# Wrinkles.net
KiCad netlist of a schematic drawn in EAGLE
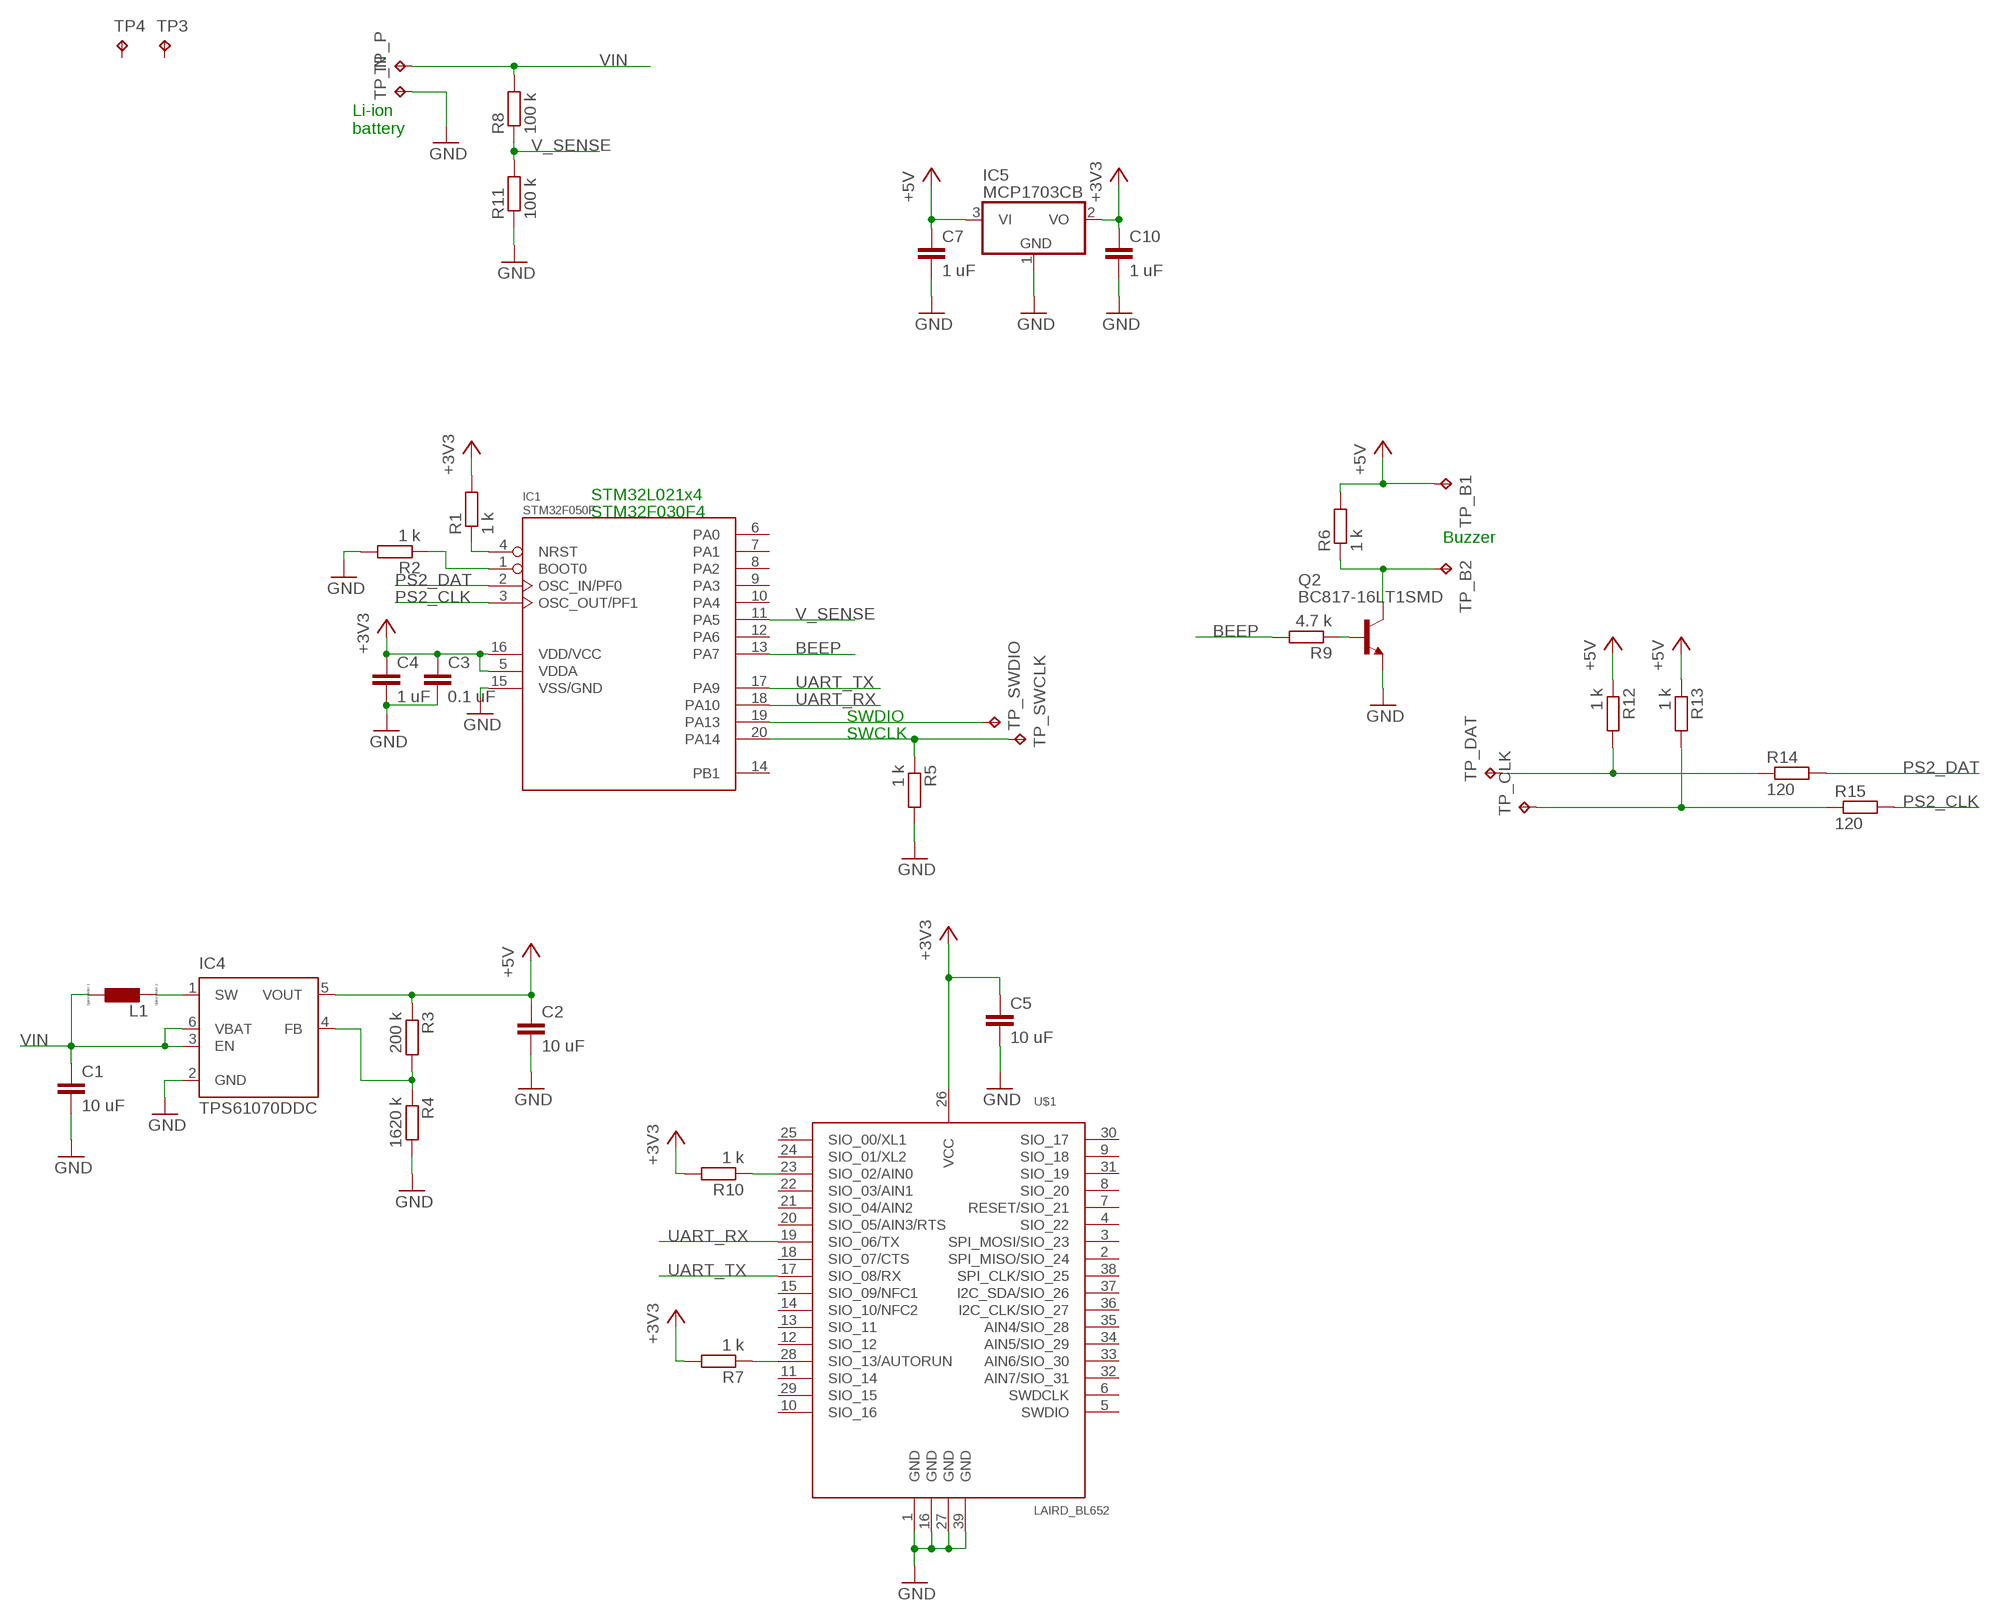
[diagram p0: schematic, sheet 1]

(export (version "E")
  (design (tool "Eeschema 10.0.6"))
  (components
    (comp (ref "C1")
      (value "10 uF")
      (footprint "eagle-import:C0603")
      (libsource (lib "eagle-import") (part "C-EUC0603"))
    )
    (comp (ref "C2")
      (value "10 uF")
      (footprint "eagle-import:C0603")
      (libsource (lib "eagle-import") (part "C-EUC0603"))
    )
    (comp (ref "C3")
      (value "0.1 uF")
      (footprint "eagle-import:C0402")
      (libsource (lib "eagle-import") (part "C-EUC0402"))
    )
    (comp (ref "C4")
      (value "1 uF")
      (footprint "eagle-import:C0402")
      (libsource (lib "eagle-import") (part "C-EUC0402"))
    )
    (comp (ref "C5")
      (value "10 uF")
      (footprint "eagle-import:C0603")
      (libsource (lib "eagle-import") (part "C-EUC0603"))
    )
    (comp (ref "C7")
      (value "1 uF")
      (footprint "eagle-import:C0402")
      (libsource (lib "eagle-import") (part "C-EUC0402"))
    )
    (comp (ref "C10")
      (value "1 uF")
      (footprint "eagle-import:C0402")
      (libsource (lib "eagle-import") (part "C-EUC0402"))
    )
    (comp (ref "IC1")
      (value "STM32F050F")
      (footprint "eagle-import:TSSOP20")
      (libsource (lib "eagle-import") (part "STM32F050F"))
    )
    (comp (ref "IC4")
      (value "TPS61070DDC")
      (footprint "eagle-import:TSOT23-6_DDC")
      (fields (field (name "MPN") "TPS61070DDCR"))
      (libsource (lib "eagle-import") (part "TPS6107DDC0"))
    )
    (comp (ref "IC5")
      (value "MCP1703CB")
      (footprint "eagle-import:SOT23")
      (libsource (lib "eagle-import") (part "MCP1703CB"))
    )
    (comp (ref "L1")
      (value "LL5038P")
      (footprint "eagle-import:L5038P")
      (libsource (lib "eagle-import") (part "LL5038P"))
    )
    (comp (ref "Q2")
      (value "BC817-16LT1SMD")
      (footprint "eagle-import:SOT23-BEC")
      (libsource (lib "eagle-import") (part "BC817SMD-16LT1"))
    )
    (comp (ref "R1")
      (value "1 k")
      (footprint "eagle-import:R0402")
      (libsource (lib "eagle-import") (part "R-EU_R0402"))
    )
    (comp (ref "R2")
      (value "1 k")
      (footprint "eagle-import:R0402")
      (libsource (lib "eagle-import") (part "R-EU_R0402"))
    )
    (comp (ref "R3")
      (value "200 k")
      (footprint "eagle-import:R0603")
      (libsource (lib "eagle-import") (part "R-EU_R0603"))
    )
    (comp (ref "R4")
      (value "1620 k")
      (footprint "eagle-import:R0603")
      (libsource (lib "eagle-import") (part "R-EU_R0603"))
    )
    (comp (ref "R5")
      (value "1 k")
      (footprint "eagle-import:R0402")
      (libsource (lib "eagle-import") (part "R-EU_R0402"))
    )
    (comp (ref "R6")
      (value "1 k")
      (footprint "eagle-import:R0402")
      (libsource (lib "eagle-import") (part "R-EU_R0402"))
    )
    (comp (ref "R7")
      (value "1 k")
      (footprint "eagle-import:R0402")
      (libsource (lib "eagle-import") (part "R-EU_R0402"))
    )
    (comp (ref "R8")
      (value "100 k")
      (footprint "eagle-import:R0402")
      (libsource (lib "eagle-import") (part "R-EU_R0402"))
    )
    (comp (ref "R9")
      (value "4.7 k")
      (footprint "eagle-import:R0402")
      (libsource (lib "eagle-import") (part "R-EU_R0402"))
    )
    (comp (ref "R10")
      (value "1 k")
      (footprint "eagle-import:R0402")
      (libsource (lib "eagle-import") (part "R-EU_R0402"))
    )
    (comp (ref "R11")
      (value "100 k")
      (footprint "eagle-import:R0402")
      (libsource (lib "eagle-import") (part "R-EU_R0402"))
    )
    (comp (ref "R12")
      (value "1 k")
      (footprint "eagle-import:R0402")
      (libsource (lib "eagle-import") (part "R-EU_R0402"))
    )
    (comp (ref "R13")
      (value "1 k")
      (footprint "eagle-import:R0402")
      (libsource (lib "eagle-import") (part "R-EU_R0402"))
    )
    (comp (ref "R14")
      (value "120")
      (footprint "eagle-import:R0402")
      (libsource (lib "eagle-import") (part "R-EU_R0402"))
    )
    (comp (ref "R15")
      (value "120")
      (footprint "eagle-import:R0402")
      (libsource (lib "eagle-import") (part "R-EU_R0402"))
    )
    (comp (ref "TP3")
      (value "TPPAD1-13")
      (footprint "eagle-import:P1-13")
      (libsource (lib "eagle-import") (part "TPPAD1-13"))
    )
    (comp (ref "TP4")
      (value "TPPAD1-13")
      (footprint "eagle-import:P1-13")
      (libsource (lib "eagle-import") (part "TPPAD1-13"))
    )
    (comp (ref "TP_B1")
      (value "TPPAD1-13")
      (footprint "eagle-import:P1-13")
      (libsource (lib "eagle-import") (part "TPPAD1-13"))
    )
    (comp (ref "TP_B2")
      (value "TPPAD1-13")
      (footprint "eagle-import:P1-13")
      (libsource (lib "eagle-import") (part "TPPAD1-13"))
    )
    (comp (ref "TP_CLK")
      (value "TPTP10SQ")
      (footprint "eagle-import:TP10SQ")
      (libsource (lib "eagle-import") (part "TPTP10SQ"))
    )
    (comp (ref "TP_DAT")
      (value "TPTP10SQ")
      (footprint "eagle-import:TP10SQ")
      (libsource (lib "eagle-import") (part "TPTP10SQ"))
    )
    (comp (ref "TP_N")
      (value "TPPAD1-13")
      (footprint "eagle-import:P1-13")
      (libsource (lib "eagle-import") (part "TPPAD1-13"))
    )
    (comp (ref "TP_P")
      (value "TPPAD1-13")
      (footprint "eagle-import:P1-13")
      (libsource (lib "eagle-import") (part "TPPAD1-13"))
    )
    (comp (ref "TP_SWCLK")
      (value "TPTP10SQ")
      (footprint "eagle-import:TP10SQ")
      (libsource (lib "eagle-import") (part "TPTP10SQ"))
    )
    (comp (ref "TP_SWDIO")
      (value "TPTP10SQ")
      (footprint "eagle-import:TP10SQ")
      (libsource (lib "eagle-import") (part "TPTP10SQ"))
    )
    (comp (ref "U$1")
      (value "LAIRD_BL652")
      (footprint "eagle-import:BL652")
      (libsource (lib "eagle-import") (part "LAIRD_BL652"))
    )
  )
  (nets
    (net (code "1") (name "+3V3") (class "Default")
      (node (ref "C10") (pin "1") (pinfunction "1_1") (pintype "passive"))
      (node (ref "C3") (pin "1") (pinfunction "1_1") (pintype "passive"))
      (node (ref "C4") (pin "1") (pinfunction "1_1") (pintype "passive"))
      (node (ref "C5") (pin "1") (pinfunction "1_1") (pintype "passive"))
      (node (ref "IC1") (pin "16") (pinfunction "VDD/VCC_16") (pintype "power_in"))
      (node (ref "IC1") (pin "5") (pinfunction "VDDA_5") (pintype "power_in"))
      (node (ref "IC5") (pin "2") (pinfunction "VO_2") (pintype "passive"))
      (node (ref "R1") (pin "2") (pinfunction "2_2") (pintype "passive"))
      (node (ref "R10") (pin "2") (pinfunction "2_2") (pintype "passive"))
      (node (ref "R7") (pin "2") (pinfunction "2_2") (pintype "passive"))
      (node (ref "U$1") (pin "26") (pinfunction "VCC_26") (pintype "power_in"))
    )
    (net (code "2") (name "+5V") (class "Default")
      (node (ref "C2") (pin "1") (pinfunction "1_1") (pintype "passive"))
      (node (ref "C7") (pin "1") (pinfunction "1_1") (pintype "passive"))
      (node (ref "IC4") (pin "5") (pinfunction "VOUT_5") (pintype "passive"))
      (node (ref "IC5") (pin "3") (pinfunction "VI_3") (pintype "input"))
      (node (ref "R12") (pin "1") (pinfunction "1_1") (pintype "passive"))
      (node (ref "R13") (pin "1") (pinfunction "1_1") (pintype "passive"))
      (node (ref "R3") (pin "1") (pinfunction "1_1") (pintype "passive"))
      (node (ref "R6") (pin "2") (pinfunction "2_2") (pintype "passive"))
      (node (ref "TP_B1") (pin "TP") (pinfunction "TP_TP") (pintype "input"))
    )
    (net (code "3") (name "/BEEP") (class "Default")
      (node (ref "IC1") (pin "13") (pinfunction "PA7_13") (pintype "bidirectional"))
      (node (ref "R9") (pin "2") (pinfunction "2_2") (pintype "passive"))
    )
    (net (code "4") (name "/PS2_CLK") (class "Default")
      (node (ref "IC1") (pin "3") (pinfunction "OSC_OUT/PF1_3") (pintype "bidirectional"))
      (node (ref "R15") (pin "2") (pinfunction "2_2") (pintype "passive"))
    )
    (net (code "5") (name "/PS2_DAT") (class "Default")
      (node (ref "IC1") (pin "2") (pinfunction "OSC_IN/PF0_2") (pintype "bidirectional"))
      (node (ref "R14") (pin "2") (pinfunction "2_2") (pintype "passive"))
    )
    (net (code "6") (name "/UART_RX") (class "Default")
      (node (ref "IC1") (pin "18") (pinfunction "PA10_18") (pintype "bidirectional"))
      (node (ref "U$1") (pin "19") (pinfunction "SIO_06/TX_19") (pintype "bidirectional"))
    )
    (net (code "7") (name "/UART_TX") (class "Default")
      (node (ref "IC1") (pin "17") (pinfunction "PA9_17") (pintype "bidirectional"))
      (node (ref "U$1") (pin "17") (pinfunction "SIO_08/RX_17") (pintype "bidirectional"))
    )
    (net (code "8") (name "/VIN") (class "Default")
      (node (ref "C1") (pin "1") (pinfunction "1_1") (pintype "passive"))
      (node (ref "IC4") (pin "3") (pinfunction "EN_3") (pintype "input"))
      (node (ref "IC4") (pin "6") (pinfunction "VBAT_6") (pintype "input"))
      (node (ref "L1") (pin "1") (pinfunction "1_1") (pintype "passive"))
      (node (ref "R8") (pin "2") (pinfunction "2_2") (pintype "passive"))
      (node (ref "TP_P") (pin "TP") (pinfunction "TP_TP") (pintype "input"))
    )
    (net (code "9") (name "/V_SENSE") (class "Default")
      (node (ref "IC1") (pin "11") (pinfunction "PA5_11") (pintype "bidirectional"))
      (node (ref "R11") (pin "2") (pinfunction "2_2") (pintype "passive"))
      (node (ref "R8") (pin "1") (pinfunction "1_1") (pintype "passive"))
    )
    (net (code "10") (name "GND") (class "Default")
      (node (ref "C1") (pin "2") (pinfunction "2_2") (pintype "passive"))
      (node (ref "C10") (pin "2") (pinfunction "2_2") (pintype "passive"))
      (node (ref "C2") (pin "2") (pinfunction "2_2") (pintype "passive"))
      (node (ref "C3") (pin "2") (pinfunction "2_2") (pintype "passive"))
      (node (ref "C4") (pin "2") (pinfunction "2_2") (pintype "passive"))
      (node (ref "C5") (pin "2") (pinfunction "2_2") (pintype "passive"))
      (node (ref "C7") (pin "2") (pinfunction "2_2") (pintype "passive"))
      (node (ref "IC1") (pin "15") (pinfunction "VSS/GND_15") (pintype "power_in"))
      (node (ref "IC4") (pin "2") (pinfunction "GND_2") (pintype "power_in"))
      (node (ref "IC5") (pin "1") (pinfunction "GND_1") (pintype "passive"))
      (node (ref "Q2") (pin "E") (pinfunction "E_E") (pintype "passive"))
      (node (ref "R11") (pin "1") (pinfunction "1_1") (pintype "passive"))
      (node (ref "R2") (pin "2") (pinfunction "2_2") (pintype "passive"))
      (node (ref "R4") (pin "2") (pinfunction "2_2") (pintype "passive"))
      (node (ref "R5") (pin "2") (pinfunction "2_2") (pintype "passive"))
      (node (ref "TP_N") (pin "TP") (pinfunction "TP_TP") (pintype "input"))
      (node (ref "U$1") (pin "1") (pinfunction "GND_1") (pintype "power_in"))
      (node (ref "U$1") (pin "16") (pinfunction "GND_16") (pintype "power_in"))
      (node (ref "U$1") (pin "27") (pinfunction "GND_27") (pintype "power_in"))
      (node (ref "U$1") (pin "39") (pinfunction "GND_39") (pintype "power_in"))
    )
    (net (code "11") (name "Net-(IC1-BOOT0)") (class "Default")
      (node (ref "IC1") (pin "1") (pinfunction "BOOT0_1") (pintype "bidirectional"))
      (node (ref "R2") (pin "1") (pinfunction "1_1") (pintype "passive"))
    )
    (net (code "12") (name "Net-(IC1-NRST)") (class "Default")
      (node (ref "IC1") (pin "4") (pinfunction "NRST_4") (pintype "bidirectional"))
      (node (ref "R1") (pin "1") (pinfunction "1_1") (pintype "passive"))
    )
    (net (code "13") (name "Net-(IC1-PA13)") (class "Default")
      (node (ref "IC1") (pin "19") (pinfunction "PA13_19") (pintype "bidirectional"))
      (node (ref "TP_SWDIO") (pin "TP") (pinfunction "TP_TP") (pintype "input"))
    )
    (net (code "14") (name "Net-(IC1-PA14)") (class "Default")
      (node (ref "IC1") (pin "20") (pinfunction "PA14_20") (pintype "bidirectional"))
      (node (ref "R5") (pin "1") (pinfunction "1_1") (pintype "passive"))
      (node (ref "TP_SWCLK") (pin "TP") (pinfunction "TP_TP") (pintype "input"))
    )
    (net (code "15") (name "Net-(IC4-FB)") (class "Default")
      (node (ref "IC4") (pin "4") (pinfunction "FB_4") (pintype "input"))
      (node (ref "R3") (pin "2") (pinfunction "2_2") (pintype "passive"))
      (node (ref "R4") (pin "1") (pinfunction "1_1") (pintype "passive"))
    )
    (net (code "16") (name "Net-(IC4-SW)") (class "Default")
      (node (ref "IC4") (pin "1") (pinfunction "SW_1") (pintype "input"))
      (node (ref "L1") (pin "2") (pinfunction "2_2") (pintype "passive"))
    )
    (net (code "17") (name "Net-(Q2-PadB)") (class "Default")
      (node (ref "Q2") (pin "B") (pinfunction "B_B") (pintype "passive"))
      (node (ref "R9") (pin "1") (pinfunction "1_1") (pintype "passive"))
    )
    (net (code "18") (name "Net-(Q2-PadC)") (class "Default")
      (node (ref "Q2") (pin "C") (pinfunction "C_C") (pintype "passive"))
      (node (ref "R6") (pin "1") (pinfunction "1_1") (pintype "passive"))
      (node (ref "TP_B2") (pin "TP") (pinfunction "TP_TP") (pintype "input"))
    )
    (net (code "19") (name "Net-(R12-Pad2)") (class "Default")
      (node (ref "R12") (pin "2") (pinfunction "2_2") (pintype "passive"))
      (node (ref "R14") (pin "1") (pinfunction "1_1") (pintype "passive"))
      (node (ref "TP_DAT") (pin "TP") (pinfunction "TP_TP") (pintype "input"))
    )
    (net (code "20") (name "Net-(R13-Pad2)") (class "Default")
      (node (ref "R13") (pin "2") (pinfunction "2_2") (pintype "passive"))
      (node (ref "R15") (pin "1") (pinfunction "1_1") (pintype "passive"))
      (node (ref "TP_CLK") (pin "TP") (pinfunction "TP_TP") (pintype "input"))
    )
    (net (code "21") (name "Net-(U$1-SIO_02{slash}AIN0)") (class "Default")
      (node (ref "R10") (pin "1") (pinfunction "1_1") (pintype "passive"))
      (node (ref "U$1") (pin "23") (pinfunction "SIO_02/AIN0_23") (pintype "bidirectional"))
    )
    (net (code "22") (name "Net-(U$1-SIO_13{slash}AUTORUN)") (class "Default")
      (node (ref "R7") (pin "1") (pinfunction "1_1") (pintype "passive"))
      (node (ref "U$1") (pin "28") (pinfunction "SIO_13/AUTORUN_28") (pintype "bidirectional"))
    )
    (net (code "23") (name "unconnected-(IC1-PA0-Pad6)") (class "Default")
      (node (ref "IC1") (pin "6") (pinfunction "PA0_6") (pintype "bidirectional"))
    )
    (net (code "24") (name "unconnected-(IC1-PA1-Pad7)") (class "Default")
      (node (ref "IC1") (pin "7") (pinfunction "PA1_7") (pintype "bidirectional"))
    )
    (net (code "25") (name "unconnected-(IC1-PA2-Pad8)") (class "Default")
      (node (ref "IC1") (pin "8") (pinfunction "PA2_8") (pintype "bidirectional"))
    )
    (net (code "26") (name "unconnected-(IC1-PA3-Pad9)") (class "Default")
      (node (ref "IC1") (pin "9") (pinfunction "PA3_9") (pintype "bidirectional"))
    )
    (net (code "27") (name "unconnected-(IC1-PA4-Pad10)") (class "Default")
      (node (ref "IC1") (pin "10") (pinfunction "PA4_10") (pintype "bidirectional"))
    )
    (net (code "28") (name "unconnected-(IC1-PA6-Pad12)") (class "Default")
      (node (ref "IC1") (pin "12") (pinfunction "PA6_12") (pintype "bidirectional"))
    )
    (net (code "29") (name "unconnected-(IC1-PB1-Pad14)") (class "Default")
      (node (ref "IC1") (pin "14") (pinfunction "PB1_14") (pintype "bidirectional"))
    )
    (net (code "30") (name "unconnected-(TP3-PadTP)") (class "Default")
      (node (ref "TP3") (pin "TP") (pinfunction "TP_TP") (pintype "input"))
    )
    (net (code "31") (name "unconnected-(TP4-PadTP)") (class "Default")
      (node (ref "TP4") (pin "TP") (pinfunction "TP_TP") (pintype "input"))
    )
    (net (code "32") (name "unconnected-(U$1-AIN4{slash}SIO_28-Pad35)") (class "Default")
      (node (ref "U$1") (pin "35") (pinfunction "AIN4/SIO_28_35") (pintype "bidirectional"))
    )
    (net (code "33") (name "unconnected-(U$1-AIN5{slash}SIO_29-Pad34)") (class "Default")
      (node (ref "U$1") (pin "34") (pinfunction "AIN5/SIO_29_34") (pintype "bidirectional"))
    )
    (net (code "34") (name "unconnected-(U$1-AIN6{slash}SIO_30-Pad33)") (class "Default")
      (node (ref "U$1") (pin "33") (pinfunction "AIN6/SIO_30_33") (pintype "bidirectional"))
    )
    (net (code "35") (name "unconnected-(U$1-AIN7{slash}SIO_31-Pad32)") (class "Default")
      (node (ref "U$1") (pin "32") (pinfunction "AIN7/SIO_31_32") (pintype "bidirectional"))
    )
    (net (code "36") (name "unconnected-(U$1-I2C_CLK{slash}SIO_27-Pad36)") (class "Default")
      (node (ref "U$1") (pin "36") (pinfunction "I2C_CLK/SIO_27_36") (pintype "bidirectional"))
    )
    (net (code "37") (name "unconnected-(U$1-I2C_SDA{slash}SIO_26-Pad37)") (class "Default")
      (node (ref "U$1") (pin "37") (pinfunction "I2C_SDA/SIO_26_37") (pintype "bidirectional"))
    )
    (net (code "38") (name "unconnected-(U$1-RESET{slash}SIO_21-Pad7)") (class "Default")
      (node (ref "U$1") (pin "7") (pinfunction "RESET/SIO_21_7") (pintype "bidirectional"))
    )
    (net (code "39") (name "unconnected-(U$1-SIO_00{slash}XL1-Pad25)") (class "Default")
      (node (ref "U$1") (pin "25") (pinfunction "SIO_00/XL1_25") (pintype "bidirectional"))
    )
    (net (code "40") (name "unconnected-(U$1-SIO_01{slash}XL2-Pad24)") (class "Default")
      (node (ref "U$1") (pin "24") (pinfunction "SIO_01/XL2_24") (pintype "bidirectional"))
    )
    (net (code "41") (name "unconnected-(U$1-SIO_03{slash}AIN1-Pad22)") (class "Default")
      (node (ref "U$1") (pin "22") (pinfunction "SIO_03/AIN1_22") (pintype "bidirectional"))
    )
    (net (code "42") (name "unconnected-(U$1-SIO_04{slash}AIN2-Pad21)") (class "Default")
      (node (ref "U$1") (pin "21") (pinfunction "SIO_04/AIN2_21") (pintype "bidirectional"))
    )
    (net (code "43") (name "unconnected-(U$1-SIO_05{slash}AIN3{slash}RTS-Pad20)") (class "Default")
      (node (ref "U$1") (pin "20") (pinfunction "SIO_05/AIN3/RTS_20") (pintype "bidirectional"))
    )
    (net (code "44") (name "unconnected-(U$1-SIO_07{slash}CTS-Pad18)") (class "Default")
      (node (ref "U$1") (pin "18") (pinfunction "SIO_07/CTS_18") (pintype "bidirectional"))
    )
    (net (code "45") (name "unconnected-(U$1-SIO_09{slash}NFC1-Pad15)") (class "Default")
      (node (ref "U$1") (pin "15") (pinfunction "SIO_09/NFC1_15") (pintype "bidirectional"))
    )
    (net (code "46") (name "unconnected-(U$1-SIO_10{slash}NFC2-Pad14)") (class "Default")
      (node (ref "U$1") (pin "14") (pinfunction "SIO_10/NFC2_14") (pintype "bidirectional"))
    )
    (net (code "47") (name "unconnected-(U$1-SIO_11-Pad13)") (class "Default")
      (node (ref "U$1") (pin "13") (pinfunction "SIO_11_13") (pintype "bidirectional"))
    )
    (net (code "48") (name "unconnected-(U$1-SIO_12-Pad12)") (class "Default")
      (node (ref "U$1") (pin "12") (pinfunction "SIO_12_12") (pintype "bidirectional"))
    )
    (net (code "49") (name "unconnected-(U$1-SIO_14-Pad11)") (class "Default")
      (node (ref "U$1") (pin "11") (pinfunction "SIO_14_11") (pintype "bidirectional"))
    )
    (net (code "50") (name "unconnected-(U$1-SIO_15-Pad29)") (class "Default")
      (node (ref "U$1") (pin "29") (pinfunction "SIO_15_29") (pintype "bidirectional"))
    )
    (net (code "51") (name "unconnected-(U$1-SIO_16-Pad10)") (class "Default")
      (node (ref "U$1") (pin "10") (pinfunction "SIO_16_10") (pintype "bidirectional"))
    )
    (net (code "52") (name "unconnected-(U$1-SIO_17-Pad30)") (class "Default")
      (node (ref "U$1") (pin "30") (pinfunction "SIO_17_30") (pintype "bidirectional"))
    )
    (net (code "53") (name "unconnected-(U$1-SIO_18-Pad9)") (class "Default")
      (node (ref "U$1") (pin "9") (pinfunction "SIO_18_9") (pintype "bidirectional"))
    )
    (net (code "54") (name "unconnected-(U$1-SIO_19-Pad31)") (class "Default")
      (node (ref "U$1") (pin "31") (pinfunction "SIO_19_31") (pintype "bidirectional"))
    )
    (net (code "55") (name "unconnected-(U$1-SIO_20-Pad8)") (class "Default")
      (node (ref "U$1") (pin "8") (pinfunction "SIO_20_8") (pintype "bidirectional"))
    )
    (net (code "56") (name "unconnected-(U$1-SIO_22-Pad4)") (class "Default")
      (node (ref "U$1") (pin "4") (pinfunction "SIO_22_4") (pintype "bidirectional"))
    )
    (net (code "57") (name "unconnected-(U$1-SPI_CLK{slash}SIO_25-Pad38)") (class "Default")
      (node (ref "U$1") (pin "38") (pinfunction "SPI_CLK/SIO_25_38") (pintype "bidirectional"))
    )
    (net (code "58") (name "unconnected-(U$1-SPI_MISO{slash}SIO_24-Pad2)") (class "Default")
      (node (ref "U$1") (pin "2") (pinfunction "SPI_MISO/SIO_24_2") (pintype "bidirectional"))
    )
    (net (code "59") (name "unconnected-(U$1-SPI_MOSI{slash}SIO_23-Pad3)") (class "Default")
      (node (ref "U$1") (pin "3") (pinfunction "SPI_MOSI/SIO_23_3") (pintype "bidirectional"))
    )
    (net (code "60") (name "unconnected-(U$1-SWDCLK-Pad6)") (class "Default")
      (node (ref "U$1") (pin "6") (pinfunction "SWDCLK_6") (pintype "bidirectional"))
    )
    (net (code "61") (name "unconnected-(U$1-SWDIO-Pad5)") (class "Default")
      (node (ref "U$1") (pin "5") (pinfunction "SWDIO_5") (pintype "bidirectional"))
    )
  )
)
